# symbol.net
KiCad netlist of a schematic drawn in Altium Designer
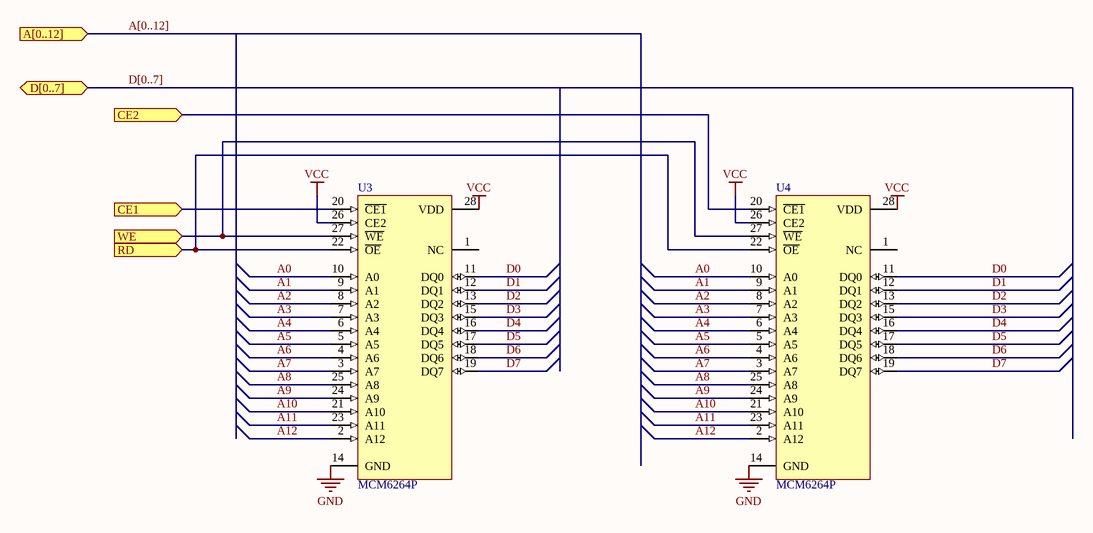
[diagram p0: 扩展存储器电路symbol.SchDoc]

(export (version "E")
  (design (tool "Eeschema 10.0.6"))
  (components
    (comp (ref "U3")
      (value "MCM6264P")
      (footprint "710B-01")
      (description "8K x 8-Bit Fast Static RAM")
      (fields (field (name "PUBLISHER") "Altium Limited"))
      (libsource (lib "Motorola Memory Static RAM") (part "MCM6264P"))
    )
    (comp (ref "U4")
      (value "MCM6264P")
      (footprint "710B-01")
      (description "8K x 8-Bit Fast Static RAM")
      (fields (field (name "PUBLISHER") "Altium Limited"))
      (libsource (lib "Motorola Memory Static RAM") (part "MCM6264P"))
    )
  )
  (nets
    (net (code "1") (name "/A0") (class "Default")
      (node (ref "U3") (pin "10") (pinfunction "A0_10") (pintype "input"))
      (node (ref "U4") (pin "10") (pinfunction "A0_10") (pintype "input"))
    )
    (net (code "2") (name "/A1") (class "Default")
      (node (ref "U3") (pin "9") (pinfunction "A1_9") (pintype "input"))
      (node (ref "U4") (pin "9") (pinfunction "A1_9") (pintype "input"))
    )
    (net (code "3") (name "/A2") (class "Default")
      (node (ref "U3") (pin "8") (pinfunction "A2_8") (pintype "input"))
      (node (ref "U4") (pin "8") (pinfunction "A2_8") (pintype "input"))
    )
    (net (code "4") (name "/A3") (class "Default")
      (node (ref "U3") (pin "7") (pinfunction "A3_7") (pintype "input"))
      (node (ref "U4") (pin "7") (pinfunction "A3_7") (pintype "input"))
    )
    (net (code "5") (name "/A4") (class "Default")
      (node (ref "U3") (pin "6") (pinfunction "A4_6") (pintype "input"))
      (node (ref "U4") (pin "6") (pinfunction "A4_6") (pintype "input"))
    )
    (net (code "6") (name "/A5") (class "Default")
      (node (ref "U3") (pin "5") (pinfunction "A5_5") (pintype "input"))
      (node (ref "U4") (pin "5") (pinfunction "A5_5") (pintype "input"))
    )
    (net (code "7") (name "/A6") (class "Default")
      (node (ref "U3") (pin "4") (pinfunction "A6_4") (pintype "input"))
      (node (ref "U4") (pin "4") (pinfunction "A6_4") (pintype "input"))
    )
    (net (code "8") (name "/A7") (class "Default")
      (node (ref "U3") (pin "3") (pinfunction "A7_3") (pintype "input"))
      (node (ref "U4") (pin "3") (pinfunction "A7_3") (pintype "input"))
    )
    (net (code "9") (name "/A8") (class "Default")
      (node (ref "U3") (pin "25") (pinfunction "A8_25") (pintype "input"))
      (node (ref "U4") (pin "25") (pinfunction "A8_25") (pintype "input"))
    )
    (net (code "10") (name "/A9") (class "Default")
      (node (ref "U3") (pin "24") (pinfunction "A9_24") (pintype "input"))
      (node (ref "U4") (pin "24") (pinfunction "A9_24") (pintype "input"))
    )
    (net (code "11") (name "/A10") (class "Default")
      (node (ref "U3") (pin "21") (pinfunction "A10_21") (pintype "input"))
      (node (ref "U4") (pin "21") (pinfunction "A10_21") (pintype "input"))
    )
    (net (code "12") (name "/A11") (class "Default")
      (node (ref "U3") (pin "23") (pinfunction "A11_23") (pintype "input"))
      (node (ref "U4") (pin "23") (pinfunction "A11_23") (pintype "input"))
    )
    (net (code "13") (name "/A12") (class "Default")
      (node (ref "U3") (pin "2") (pinfunction "A12_2") (pintype "input"))
      (node (ref "U4") (pin "2") (pinfunction "A12_2") (pintype "input"))
    )
    (net (code "15") (name "/CE1") (class "Default")
      (node (ref "U3") (pin "20") (pinfunction "~{CE1}_20") (pintype "input"))
    )
    (net (code "16") (name "/CE2") (class "Default")
      (node (ref "U4") (pin "20") (pinfunction "~{CE1}_20") (pintype "input"))
    )
    (net (code "17") (name "/D0") (class "Default")
      (node (ref "U3") (pin "11") (pinfunction "DQ0_11") (pintype "bidirectional"))
      (node (ref "U4") (pin "11") (pinfunction "DQ0_11") (pintype "bidirectional"))
    )
    (net (code "18") (name "/D1") (class "Default")
      (node (ref "U3") (pin "12") (pinfunction "DQ1_12") (pintype "bidirectional"))
      (node (ref "U4") (pin "12") (pinfunction "DQ1_12") (pintype "bidirectional"))
    )
    (net (code "19") (name "/D2") (class "Default")
      (node (ref "U3") (pin "13") (pinfunction "DQ2_13") (pintype "bidirectional"))
      (node (ref "U4") (pin "13") (pinfunction "DQ2_13") (pintype "bidirectional"))
    )
    (net (code "20") (name "/D3") (class "Default")
      (node (ref "U3") (pin "15") (pinfunction "DQ3_15") (pintype "bidirectional"))
      (node (ref "U4") (pin "15") (pinfunction "DQ3_15") (pintype "bidirectional"))
    )
    (net (code "21") (name "/D4") (class "Default")
      (node (ref "U3") (pin "16") (pinfunction "DQ4_16") (pintype "bidirectional"))
      (node (ref "U4") (pin "16") (pinfunction "DQ4_16") (pintype "bidirectional"))
    )
    (net (code "22") (name "/D5") (class "Default")
      (node (ref "U3") (pin "17") (pinfunction "DQ5_17") (pintype "bidirectional"))
      (node (ref "U4") (pin "17") (pinfunction "DQ5_17") (pintype "bidirectional"))
    )
    (net (code "23") (name "/D6") (class "Default")
      (node (ref "U3") (pin "18") (pinfunction "DQ6_18") (pintype "bidirectional"))
      (node (ref "U4") (pin "18") (pinfunction "DQ6_18") (pintype "bidirectional"))
    )
    (net (code "24") (name "/D7") (class "Default")
      (node (ref "U3") (pin "19") (pinfunction "DQ7_19") (pintype "bidirectional"))
      (node (ref "U4") (pin "19") (pinfunction "DQ7_19") (pintype "bidirectional"))
    )
    (net (code "26") (name "/RD") (class "Default")
      (node (ref "U3") (pin "22") (pinfunction "~{OE}_22") (pintype "input"))
      (node (ref "U4") (pin "22") (pinfunction "~{OE}_22") (pintype "input"))
    )
    (net (code "27") (name "/WE") (class "Default")
      (node (ref "U3") (pin "27") (pinfunction "~{WE}_27") (pintype "input"))
      (node (ref "U4") (pin "27") (pinfunction "~{WE}_27") (pintype "input"))
    )
    (net (code "28") (name "GND") (class "Default")
      (node (ref "U3") (pin "14") (pinfunction "GND_14") (pintype "power_in"))
      (node (ref "U4") (pin "14") (pinfunction "GND_14") (pintype "power_in"))
    )
    (net (code "29") (name "VCC") (class "Default")
      (node (ref "U3") (pin "26") (pinfunction "CE2_26") (pintype "input"))
      (node (ref "U3") (pin "28") (pinfunction "VDD_28") (pintype "power_in"))
      (node (ref "U4") (pin "26") (pinfunction "CE2_26") (pintype "input"))
      (node (ref "U4") (pin "28") (pinfunction "VDD_28") (pintype "power_in"))
    )
    (net (code "30") (name "unconnected-(U3-NC-Pad1)") (class "Default")
      (node (ref "U3") (pin "1") (pinfunction "NC_1") (pintype "passive"))
    )
    (net (code "31") (name "unconnected-(U4-NC-Pad1)") (class "Default")
      (node (ref "U4") (pin "1") (pinfunction "NC_1") (pintype "passive"))
    )
  )
)
